# RGBtlc.net
KiCad netlist of a schematic drawn in EAGLE
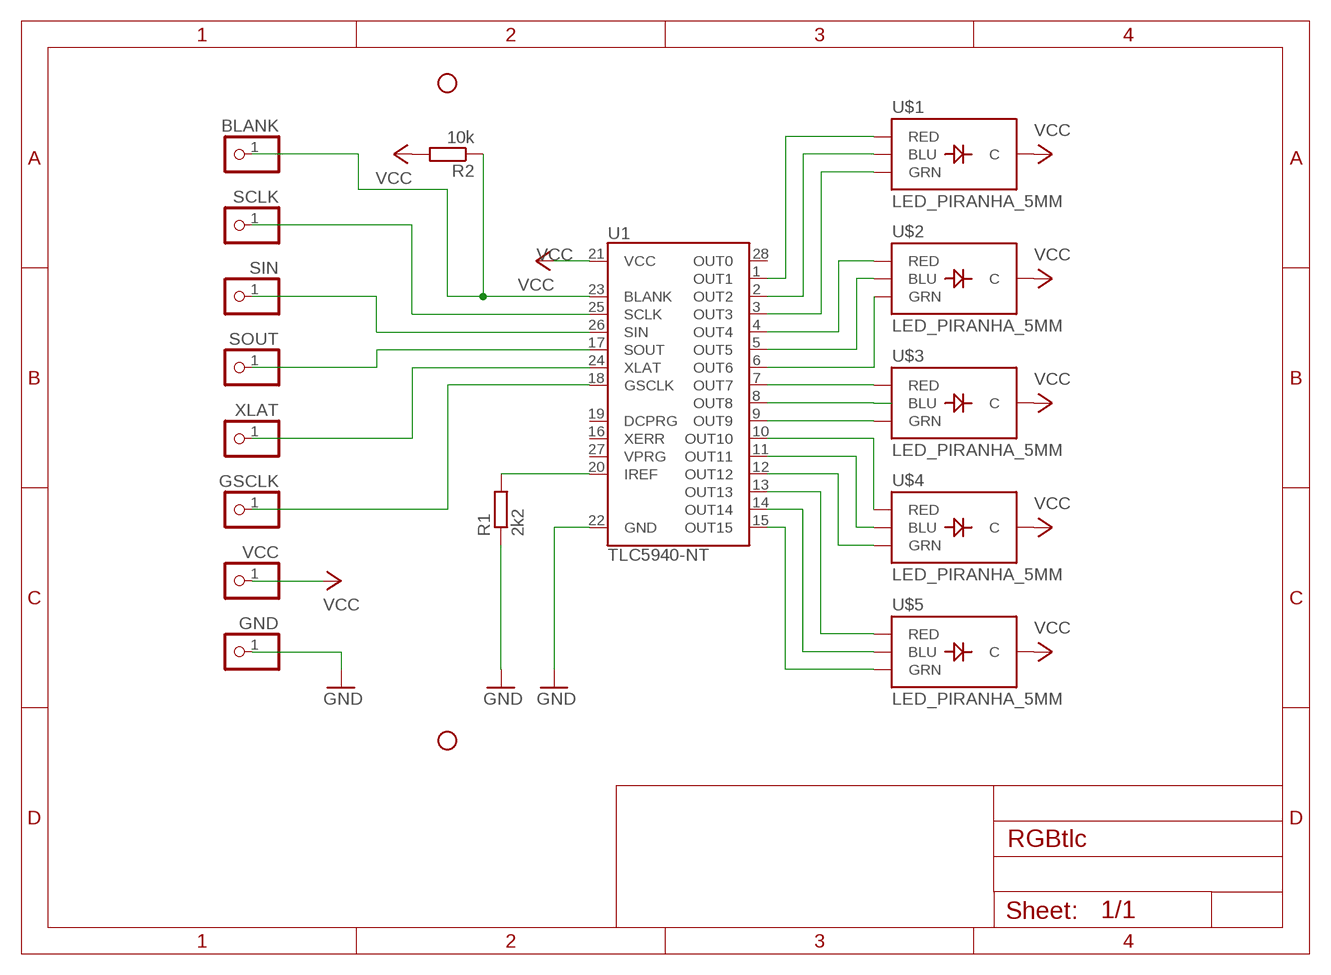
[diagram p0: schematic, sheet 1]

(export (version "E")
  (design (tool "Eeschema 10.0.6"))
  (components
    (comp (ref "BLANK")
      (value "PINHD-1X1")
      (footprint "eagle-import:1X01")
      (libsource (lib "eagle-import") (part "PINHD-1X1"))
    )
    (comp (ref "GND")
      (value "PINHD-1X1")
      (footprint "eagle-import:1X01")
      (libsource (lib "eagle-import") (part "PINHD-1X1"))
    )
    (comp (ref "GSCLK")
      (value "PINHD-1X1")
      (footprint "eagle-import:1X01")
      (libsource (lib "eagle-import") (part "PINHD-1X1"))
    )
    (comp (ref "JP1")
      (value "STAND-OFF")
      (footprint "eagle-import:STAND-OFF")
      (libsource (lib "eagle-import") (part "STAND-OFF"))
    )
    (comp (ref "JP4")
      (value "STAND-OFF")
      (footprint "eagle-import:STAND-OFF")
      (libsource (lib "eagle-import") (part "STAND-OFF"))
    )
    (comp (ref "R1")
      (value "2k2")
      (footprint "eagle-import:0207_7")
      (libsource (lib "eagle-import") (part "R-EU_0207/7"))
    )
    (comp (ref "R2")
      (value "10k")
      (footprint "eagle-import:0207_7")
      (libsource (lib "eagle-import") (part "R-EU_0207/7"))
    )
    (comp (ref "SCLK")
      (value "PINHD-1X1")
      (footprint "eagle-import:1X01")
      (libsource (lib "eagle-import") (part "PINHD-1X1"))
    )
    (comp (ref "SIN")
      (value "PINHD-1X1")
      (footprint "eagle-import:1X01")
      (libsource (lib "eagle-import") (part "PINHD-1X1"))
    )
    (comp (ref "SOUT")
      (value "PINHD-1X1")
      (footprint "eagle-import:1X01")
      (libsource (lib "eagle-import") (part "PINHD-1X1"))
    )
    (comp (ref "U$1")
      (value "LED_PIRANHA_5MM")
      (footprint "eagle-import:LED_PIRANHA_5MM")
      (libsource (lib "eagle-import") (part "LED_PIRANHA_5MM"))
    )
    (comp (ref "U$2")
      (value "LED_PIRANHA_5MM")
      (footprint "eagle-import:LED_PIRANHA_5MM")
      (libsource (lib "eagle-import") (part "LED_PIRANHA_5MM"))
    )
    (comp (ref "U$3")
      (value "LED_PIRANHA_5MM")
      (footprint "eagle-import:LED_PIRANHA_5MM")
      (libsource (lib "eagle-import") (part "LED_PIRANHA_5MM"))
    )
    (comp (ref "U$4")
      (value "LED_PIRANHA_5MM")
      (footprint "eagle-import:LED_PIRANHA_5MM")
      (libsource (lib "eagle-import") (part "LED_PIRANHA_5MM"))
    )
    (comp (ref "U$5")
      (value "LED_PIRANHA_5MM")
      (footprint "eagle-import:LED_PIRANHA_5MM")
      (libsource (lib "eagle-import") (part "LED_PIRANHA_5MM"))
    )
    (comp (ref "U1")
      (value "TLC5940-NT")
      (footprint "eagle-import:DIL28-3")
      (libsource (lib "eagle-import") (part "TLC5940-NT"))
    )
    (comp (ref "VCC")
      (value "PINHD-1X1")
      (footprint "eagle-import:1X01")
      (libsource (lib "eagle-import") (part "PINHD-1X1"))
    )
    (comp (ref "XLAT")
      (value "PINHD-1X1")
      (footprint "eagle-import:1X01")
      (libsource (lib "eagle-import") (part "PINHD-1X1"))
    )
  )
  (nets
    (net (code "1") (name "GND") (class "Default")
      (node (ref "GND") (pin "1") (pinfunction "1_1") (pintype "passive"))
      (node (ref "R1") (pin "1") (pinfunction "1_1") (pintype "passive"))
      (node (ref "U1") (pin "22") (pinfunction "GND_22") (pintype "bidirectional"))
    )
    (net (code "2") (name "Net-(U$1-BLU)") (class "Default")
      (node (ref "U$1") (pin "B") (pinfunction "BLU_B") (pintype "bidirectional"))
      (node (ref "U1") (pin "2") (pinfunction "OUT2_2") (pintype "bidirectional"))
    )
    (net (code "3") (name "Net-(U$1-GRN)") (class "Default")
      (node (ref "U$1") (pin "G") (pinfunction "GRN_G") (pintype "bidirectional"))
      (node (ref "U1") (pin "3") (pinfunction "OUT3_3") (pintype "bidirectional"))
    )
    (net (code "4") (name "Net-(U$1-RED)") (class "Default")
      (node (ref "U$1") (pin "R") (pinfunction "RED_R") (pintype "bidirectional"))
      (node (ref "U1") (pin "1") (pinfunction "OUT1_1") (pintype "bidirectional"))
    )
    (net (code "5") (name "Net-(U$2-BLU)") (class "Default")
      (node (ref "U$2") (pin "B") (pinfunction "BLU_B") (pintype "bidirectional"))
      (node (ref "U1") (pin "5") (pinfunction "OUT5_5") (pintype "bidirectional"))
    )
    (net (code "6") (name "Net-(U$2-GRN)") (class "Default")
      (node (ref "U$2") (pin "G") (pinfunction "GRN_G") (pintype "bidirectional"))
      (node (ref "U1") (pin "6") (pinfunction "OUT6_6") (pintype "bidirectional"))
    )
    (net (code "7") (name "Net-(U$2-RED)") (class "Default")
      (node (ref "U$2") (pin "R") (pinfunction "RED_R") (pintype "bidirectional"))
      (node (ref "U1") (pin "4") (pinfunction "OUT4_4") (pintype "bidirectional"))
    )
    (net (code "8") (name "Net-(U$3-BLU)") (class "Default")
      (node (ref "U$3") (pin "B") (pinfunction "BLU_B") (pintype "bidirectional"))
      (node (ref "U1") (pin "8") (pinfunction "OUT8_8") (pintype "bidirectional"))
    )
    (net (code "9") (name "Net-(U$3-GRN)") (class "Default")
      (node (ref "U$3") (pin "G") (pinfunction "GRN_G") (pintype "bidirectional"))
      (node (ref "U1") (pin "9") (pinfunction "OUT9_9") (pintype "bidirectional"))
    )
    (net (code "10") (name "Net-(U$3-RED)") (class "Default")
      (node (ref "U$3") (pin "R") (pinfunction "RED_R") (pintype "bidirectional"))
      (node (ref "U1") (pin "7") (pinfunction "OUT7_7") (pintype "bidirectional"))
    )
    (net (code "11") (name "Net-(U$4-BLU)") (class "Default")
      (node (ref "U$4") (pin "B") (pinfunction "BLU_B") (pintype "bidirectional"))
      (node (ref "U1") (pin "11") (pinfunction "OUT11_11") (pintype "bidirectional"))
    )
    (net (code "12") (name "Net-(U$4-GRN)") (class "Default")
      (node (ref "U$4") (pin "G") (pinfunction "GRN_G") (pintype "bidirectional"))
      (node (ref "U1") (pin "12") (pinfunction "OUT12_12") (pintype "bidirectional"))
    )
    (net (code "13") (name "Net-(U$4-RED)") (class "Default")
      (node (ref "U$4") (pin "R") (pinfunction "RED_R") (pintype "bidirectional"))
      (node (ref "U1") (pin "10") (pinfunction "OUT10_10") (pintype "bidirectional"))
    )
    (net (code "14") (name "Net-(U$5-BLU)") (class "Default")
      (node (ref "U$5") (pin "B") (pinfunction "BLU_B") (pintype "bidirectional"))
      (node (ref "U1") (pin "14") (pinfunction "OUT14_14") (pintype "bidirectional"))
    )
    (net (code "15") (name "Net-(U$5-GRN)") (class "Default")
      (node (ref "U$5") (pin "G") (pinfunction "GRN_G") (pintype "bidirectional"))
      (node (ref "U1") (pin "15") (pinfunction "OUT15_15") (pintype "bidirectional"))
    )
    (net (code "16") (name "Net-(U$5-RED)") (class "Default")
      (node (ref "U$5") (pin "R") (pinfunction "RED_R") (pintype "bidirectional"))
      (node (ref "U1") (pin "13") (pinfunction "OUT13_13") (pintype "bidirectional"))
    )
    (net (code "17") (name "Net-(U1-BLANK)") (class "Default")
      (node (ref "BLANK") (pin "1") (pinfunction "1_1") (pintype "passive"))
      (node (ref "R2") (pin "1") (pinfunction "1_1") (pintype "passive"))
      (node (ref "U1") (pin "23") (pinfunction "BLANK_23") (pintype "bidirectional"))
    )
    (net (code "18") (name "Net-(U1-GSCLK)") (class "Default")
      (node (ref "GSCLK") (pin "1") (pinfunction "1_1") (pintype "passive"))
      (node (ref "U1") (pin "18") (pinfunction "GSCLK_18") (pintype "bidirectional"))
    )
    (net (code "19") (name "Net-(U1-IREF)") (class "Default")
      (node (ref "R1") (pin "2") (pinfunction "2_2") (pintype "passive"))
      (node (ref "U1") (pin "20") (pinfunction "IREF_20") (pintype "bidirectional"))
    )
    (net (code "20") (name "Net-(U1-SCLK)") (class "Default")
      (node (ref "SCLK") (pin "1") (pinfunction "1_1") (pintype "passive"))
      (node (ref "U1") (pin "25") (pinfunction "SCLK_25") (pintype "bidirectional"))
    )
    (net (code "21") (name "Net-(U1-SIN)") (class "Default")
      (node (ref "SIN") (pin "1") (pinfunction "1_1") (pintype "passive"))
      (node (ref "U1") (pin "26") (pinfunction "SIN_26") (pintype "bidirectional"))
    )
    (net (code "22") (name "Net-(U1-SOUT)") (class "Default")
      (node (ref "SOUT") (pin "1") (pinfunction "1_1") (pintype "passive"))
      (node (ref "U1") (pin "17") (pinfunction "SOUT_17") (pintype "bidirectional"))
    )
    (net (code "23") (name "Net-(U1-XLAT)") (class "Default")
      (node (ref "U1") (pin "24") (pinfunction "XLAT_24") (pintype "bidirectional"))
      (node (ref "XLAT") (pin "1") (pinfunction "1_1") (pintype "passive"))
    )
    (net (code "24") (name "VCC") (class "Default")
      (node (ref "R2") (pin "2") (pinfunction "2_2") (pintype "passive"))
      (node (ref "U$1") (pin "-") (pinfunction "C_-") (pintype "bidirectional"))
      (node (ref "U$2") (pin "-") (pinfunction "C_-") (pintype "bidirectional"))
      (node (ref "U$3") (pin "-") (pinfunction "C_-") (pintype "bidirectional"))
      (node (ref "U$4") (pin "-") (pinfunction "C_-") (pintype "bidirectional"))
      (node (ref "U$5") (pin "-") (pinfunction "C_-") (pintype "bidirectional"))
      (node (ref "U1") (pin "21") (pinfunction "VCC_21") (pintype "bidirectional"))
      (node (ref "VCC") (pin "1") (pinfunction "1_1") (pintype "passive"))
    )
    (net (code "25") (name "unconnected-(U1-DCPRG-Pad19)") (class "Default")
      (node (ref "U1") (pin "19") (pinfunction "DCPRG_19") (pintype "bidirectional"))
    )
    (net (code "26") (name "unconnected-(U1-OUT0-Pad28)") (class "Default")
      (node (ref "U1") (pin "28") (pinfunction "OUT0_28") (pintype "bidirectional"))
    )
    (net (code "27") (name "unconnected-(U1-VPRG-Pad27)") (class "Default")
      (node (ref "U1") (pin "27") (pinfunction "VPRG_27") (pintype "bidirectional"))
    )
    (net (code "28") (name "unconnected-(U1-XERR-Pad16)") (class "Default")
      (node (ref "U1") (pin "16") (pinfunction "XERR_16") (pintype "bidirectional"))
    )
  )
)
